# esphome-schalter-icmodul.net
KiCad netlist of a schematic drawn in EAGLE
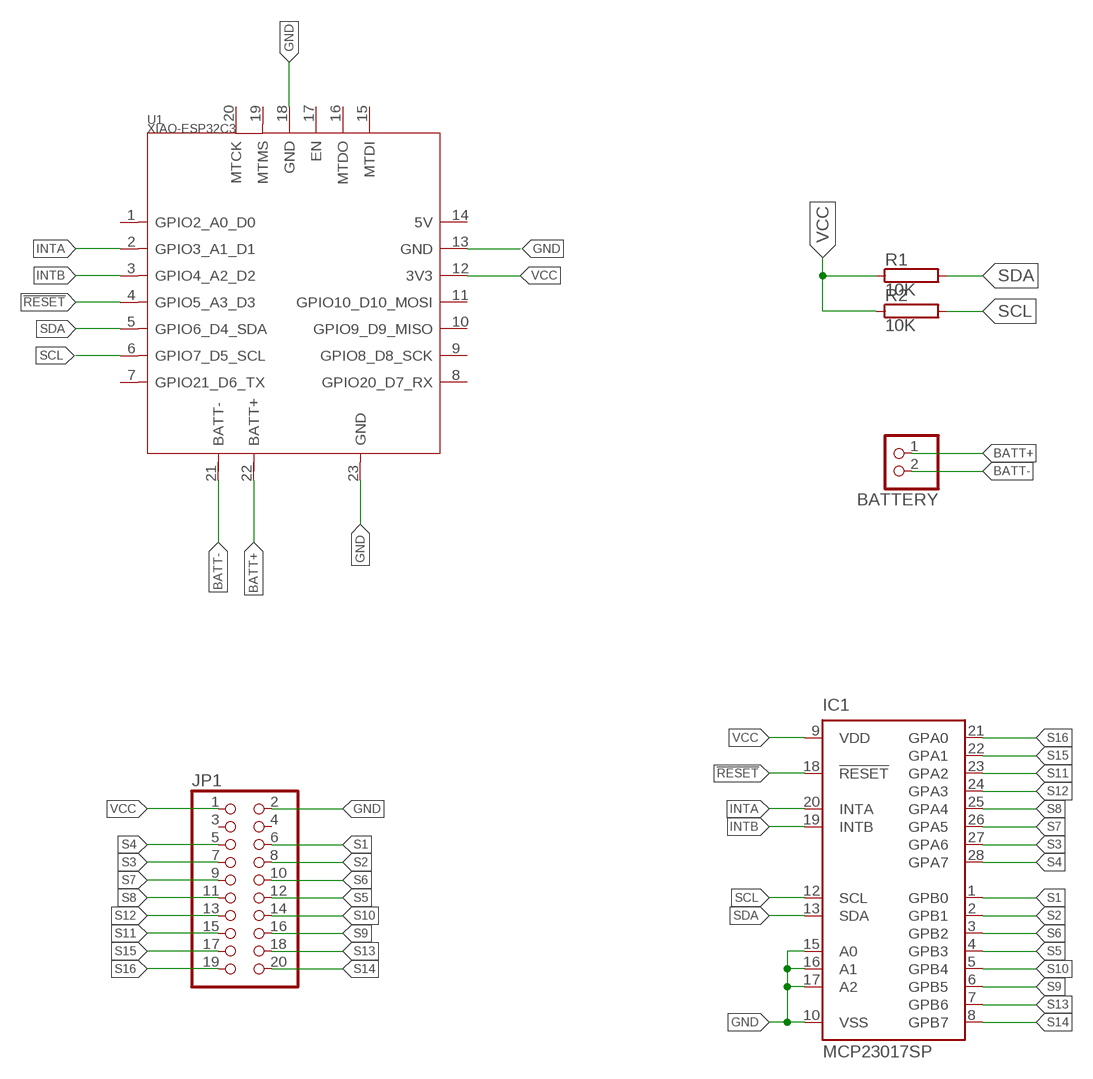
[diagram p0: schematic, sheet 1]

(export (version "E")
  (design (tool "Eeschema 10.0.6"))
  (components
    (comp (ref "BATTERY")
      (value "JST_2PIN-SMT")
      (footprint "eagle-import:JST-PH-2-SMT")
      (libsource (lib "eagle-import") (part "JST_2PIN-SMT"))
    )
    (comp (ref "IC1")
      (value "MCP23017SP")
      (footprint "eagle-import:DIL28-3")
      (fields (field (name "MF") "MICROCHIP") (field (name "MPN") "MCP23017-E/SP"))
      (libsource (lib "eagle-import") (part "MCP23017SP"))
    )
    (comp (ref "JP1")
      (value "PINHD-2X10")
      (footprint "eagle-import:2X10")
      (libsource (lib "eagle-import") (part "PINHD-2X10"))
    )
    (comp (ref "R1")
      (value "10K")
      (footprint "eagle-import:CA0001")
      (libsource (lib "eagle-import") (part "RCA0001"))
    )
    (comp (ref "R2")
      (value "10K")
      (footprint "eagle-import:CA0001")
      (libsource (lib "eagle-import") (part "RCA0001"))
    )
    (comp (ref "U1")
      (value "XIAO-ESP32C3")
      (footprint "eagle-import:XIAO-ESP32C3-MODULE14P-2.54-21X17.8MM")
      (libsource (lib "eagle-import") (part "XIAO-ESP32C3"))
    )
  )
  (nets
    (net (code "1") (name "/~{RESET}") (class "Default")
      (node (ref "IC1") (pin "18") (pinfunction "~{RESET}_18") (pintype "input"))
      (node (ref "U1") (pin "4") (pinfunction "GPIO5_A3_D3_4") (pintype "bidirectional"))
    )
    (net (code "2") (name "BATT+") (class "Default")
      (node (ref "BATTERY") (pin "1") (pinfunction "2_1") (pintype "passive"))
      (node (ref "U1") (pin "22") (pinfunction "BATT+_22") (pintype "bidirectional"))
    )
    (net (code "3") (name "BATT-") (class "Default")
      (node (ref "BATTERY") (pin "2") (pinfunction "1_2") (pintype "passive"))
      (node (ref "U1") (pin "21") (pinfunction "BATT-_21") (pintype "bidirectional"))
    )
    (net (code "4") (name "GND") (class "Default")
      (node (ref "IC1") (pin "10") (pinfunction "VSS_10") (pintype "power_in"))
      (node (ref "IC1") (pin "15") (pinfunction "A0_15") (pintype "input"))
      (node (ref "IC1") (pin "16") (pinfunction "A1_16") (pintype "input"))
      (node (ref "IC1") (pin "17") (pinfunction "A2_17") (pintype "input"))
      (node (ref "JP1") (pin "2") (pinfunction "2_2") (pintype "passive"))
      (node (ref "U1") (pin "13") (pinfunction "GND_13") (pintype "bidirectional"))
      (node (ref "U1") (pin "18") (pinfunction "GND_18") (pintype "bidirectional"))
      (node (ref "U1") (pin "23") (pinfunction "GND_23") (pintype "bidirectional"))
    )
    (net (code "5") (name "INTA") (class "Default")
      (node (ref "IC1") (pin "20") (pinfunction "INTA_20") (pintype "output"))
      (node (ref "U1") (pin "2") (pinfunction "GPIO3_A1_D1_2") (pintype "bidirectional"))
    )
    (net (code "6") (name "INTB") (class "Default")
      (node (ref "IC1") (pin "19") (pinfunction "INTB_19") (pintype "output"))
      (node (ref "U1") (pin "3") (pinfunction "GPIO4_A2_D2_3") (pintype "bidirectional"))
    )
    (net (code "7") (name "S1") (class "Default")
      (node (ref "IC1") (pin "1") (pinfunction "GPB0_1") (pintype "bidirectional"))
      (node (ref "JP1") (pin "6") (pinfunction "6_6") (pintype "passive"))
    )
    (net (code "8") (name "S2") (class "Default")
      (node (ref "IC1") (pin "2") (pinfunction "GPB1_2") (pintype "bidirectional"))
      (node (ref "JP1") (pin "8") (pinfunction "8_8") (pintype "passive"))
    )
    (net (code "9") (name "S3") (class "Default")
      (node (ref "IC1") (pin "27") (pinfunction "GPA6_27") (pintype "bidirectional"))
      (node (ref "JP1") (pin "7") (pinfunction "7_7") (pintype "passive"))
    )
    (net (code "10") (name "S4") (class "Default")
      (node (ref "IC1") (pin "28") (pinfunction "GPA7_28") (pintype "bidirectional"))
      (node (ref "JP1") (pin "5") (pinfunction "5_5") (pintype "passive"))
    )
    (net (code "11") (name "S5") (class "Default")
      (node (ref "IC1") (pin "4") (pinfunction "GPB3_4") (pintype "bidirectional"))
      (node (ref "JP1") (pin "12") (pinfunction "12_12") (pintype "passive"))
    )
    (net (code "12") (name "S6") (class "Default")
      (node (ref "IC1") (pin "3") (pinfunction "GPB2_3") (pintype "bidirectional"))
      (node (ref "JP1") (pin "10") (pinfunction "10_10") (pintype "passive"))
    )
    (net (code "13") (name "S7") (class "Default")
      (node (ref "IC1") (pin "26") (pinfunction "GPA5_26") (pintype "bidirectional"))
      (node (ref "JP1") (pin "9") (pinfunction "9_9") (pintype "passive"))
    )
    (net (code "14") (name "S8") (class "Default")
      (node (ref "IC1") (pin "25") (pinfunction "GPA4_25") (pintype "bidirectional"))
      (node (ref "JP1") (pin "11") (pinfunction "11_11") (pintype "passive"))
    )
    (net (code "15") (name "S9") (class "Default")
      (node (ref "IC1") (pin "6") (pinfunction "GPB5_6") (pintype "bidirectional"))
      (node (ref "JP1") (pin "16") (pinfunction "16_16") (pintype "passive"))
    )
    (net (code "16") (name "S10") (class "Default")
      (node (ref "IC1") (pin "5") (pinfunction "GPB4_5") (pintype "bidirectional"))
      (node (ref "JP1") (pin "14") (pinfunction "14_14") (pintype "passive"))
    )
    (net (code "17") (name "S11") (class "Default")
      (node (ref "IC1") (pin "23") (pinfunction "GPA2_23") (pintype "bidirectional"))
      (node (ref "JP1") (pin "15") (pinfunction "15_15") (pintype "passive"))
    )
    (net (code "18") (name "S12") (class "Default")
      (node (ref "IC1") (pin "24") (pinfunction "GPA3_24") (pintype "bidirectional"))
      (node (ref "JP1") (pin "13") (pinfunction "13_13") (pintype "passive"))
    )
    (net (code "19") (name "S13") (class "Default")
      (node (ref "IC1") (pin "7") (pinfunction "GPB6_7") (pintype "bidirectional"))
      (node (ref "JP1") (pin "18") (pinfunction "18_18") (pintype "passive"))
    )
    (net (code "20") (name "S14") (class "Default")
      (node (ref "IC1") (pin "8") (pinfunction "GPB7_8") (pintype "bidirectional"))
      (node (ref "JP1") (pin "20") (pinfunction "20_20") (pintype "passive"))
    )
    (net (code "21") (name "S15") (class "Default")
      (node (ref "IC1") (pin "22") (pinfunction "GPA1_22") (pintype "bidirectional"))
      (node (ref "JP1") (pin "17") (pinfunction "17_17") (pintype "passive"))
    )
    (net (code "22") (name "S16") (class "Default")
      (node (ref "IC1") (pin "21") (pinfunction "GPA0_21") (pintype "bidirectional"))
      (node (ref "JP1") (pin "19") (pinfunction "19_19") (pintype "passive"))
    )
    (net (code "23") (name "SCL") (class "Default")
      (node (ref "IC1") (pin "12") (pinfunction "SCL_12") (pintype "input"))
      (node (ref "R2") (pin "2") (pinfunction "2_2") (pintype "passive"))
      (node (ref "U1") (pin "6") (pinfunction "GPIO7_D5_SCL_6") (pintype "bidirectional"))
    )
    (net (code "24") (name "SDA") (class "Default")
      (node (ref "IC1") (pin "13") (pinfunction "SDA_13") (pintype "bidirectional"))
      (node (ref "R1") (pin "2") (pinfunction "2_2") (pintype "passive"))
      (node (ref "U1") (pin "5") (pinfunction "GPIO6_D4_SDA_5") (pintype "bidirectional"))
    )
    (net (code "25") (name "VCC") (class "Default")
      (node (ref "IC1") (pin "9") (pinfunction "VDD_9") (pintype "power_in"))
      (node (ref "JP1") (pin "1") (pinfunction "1_1") (pintype "passive"))
      (node (ref "R1") (pin "1") (pinfunction "1_1") (pintype "passive"))
      (node (ref "R2") (pin "1") (pinfunction "1_1") (pintype "passive"))
      (node (ref "U1") (pin "12") (pinfunction "3V3_12") (pintype "bidirectional"))
    )
    (net (code "26") (name "unconnected-(JP1-Pad3)") (class "Default")
      (node (ref "JP1") (pin "3") (pinfunction "3_3") (pintype "passive"))
    )
    (net (code "27") (name "unconnected-(JP1-Pad4)") (class "Default")
      (node (ref "JP1") (pin "4") (pinfunction "4_4") (pintype "passive"))
    )
    (net (code "28") (name "unconnected-(U1-5V-Pad14)") (class "Default")
      (node (ref "U1") (pin "14") (pinfunction "5V_14") (pintype "bidirectional"))
    )
    (net (code "29") (name "unconnected-(U1-EN-Pad17)") (class "Default")
      (node (ref "U1") (pin "17") (pinfunction "EN_17") (pintype "bidirectional"))
    )
    (net (code "30") (name "unconnected-(U1-GPIO2_A0_D0-Pad1)") (class "Default")
      (node (ref "U1") (pin "1") (pinfunction "GPIO2_A0_D0_1") (pintype "bidirectional"))
    )
    (net (code "31") (name "unconnected-(U1-GPIO8_D8_SCK-Pad9)") (class "Default")
      (node (ref "U1") (pin "9") (pinfunction "GPIO8_D8_SCK_9") (pintype "bidirectional"))
    )
    (net (code "32") (name "unconnected-(U1-GPIO9_D9_MISO-Pad10)") (class "Default")
      (node (ref "U1") (pin "10") (pinfunction "GPIO9_D9_MISO_10") (pintype "bidirectional"))
    )
    (net (code "33") (name "unconnected-(U1-GPIO10_D10_MOSI-Pad11)") (class "Default")
      (node (ref "U1") (pin "11") (pinfunction "GPIO10_D10_MOSI_11") (pintype "bidirectional"))
    )
    (net (code "34") (name "unconnected-(U1-GPIO20_D7_RX-Pad8)") (class "Default")
      (node (ref "U1") (pin "8") (pinfunction "GPIO20_D7_RX_8") (pintype "bidirectional"))
    )
    (net (code "35") (name "unconnected-(U1-GPIO21_D6_TX-Pad7)") (class "Default")
      (node (ref "U1") (pin "7") (pinfunction "GPIO21_D6_TX_7") (pintype "bidirectional"))
    )
    (net (code "36") (name "unconnected-(U1-MTCK-Pad20)") (class "Default")
      (node (ref "U1") (pin "20") (pinfunction "MTCK_20") (pintype "bidirectional"))
    )
    (net (code "37") (name "unconnected-(U1-MTDI-Pad15)") (class "Default")
      (node (ref "U1") (pin "15") (pinfunction "MTDI_15") (pintype "bidirectional"))
    )
    (net (code "38") (name "unconnected-(U1-MTDO-Pad16)") (class "Default")
      (node (ref "U1") (pin "16") (pinfunction "MTDO_16") (pintype "bidirectional"))
    )
    (net (code "39") (name "unconnected-(U1-MTMS-Pad19)") (class "Default")
      (node (ref "U1") (pin "19") (pinfunction "MTMS_19") (pintype "bidirectional"))
    )
  )
)
